# TopLevel.net
KiCad netlist of a schematic drawn in Altium Designer
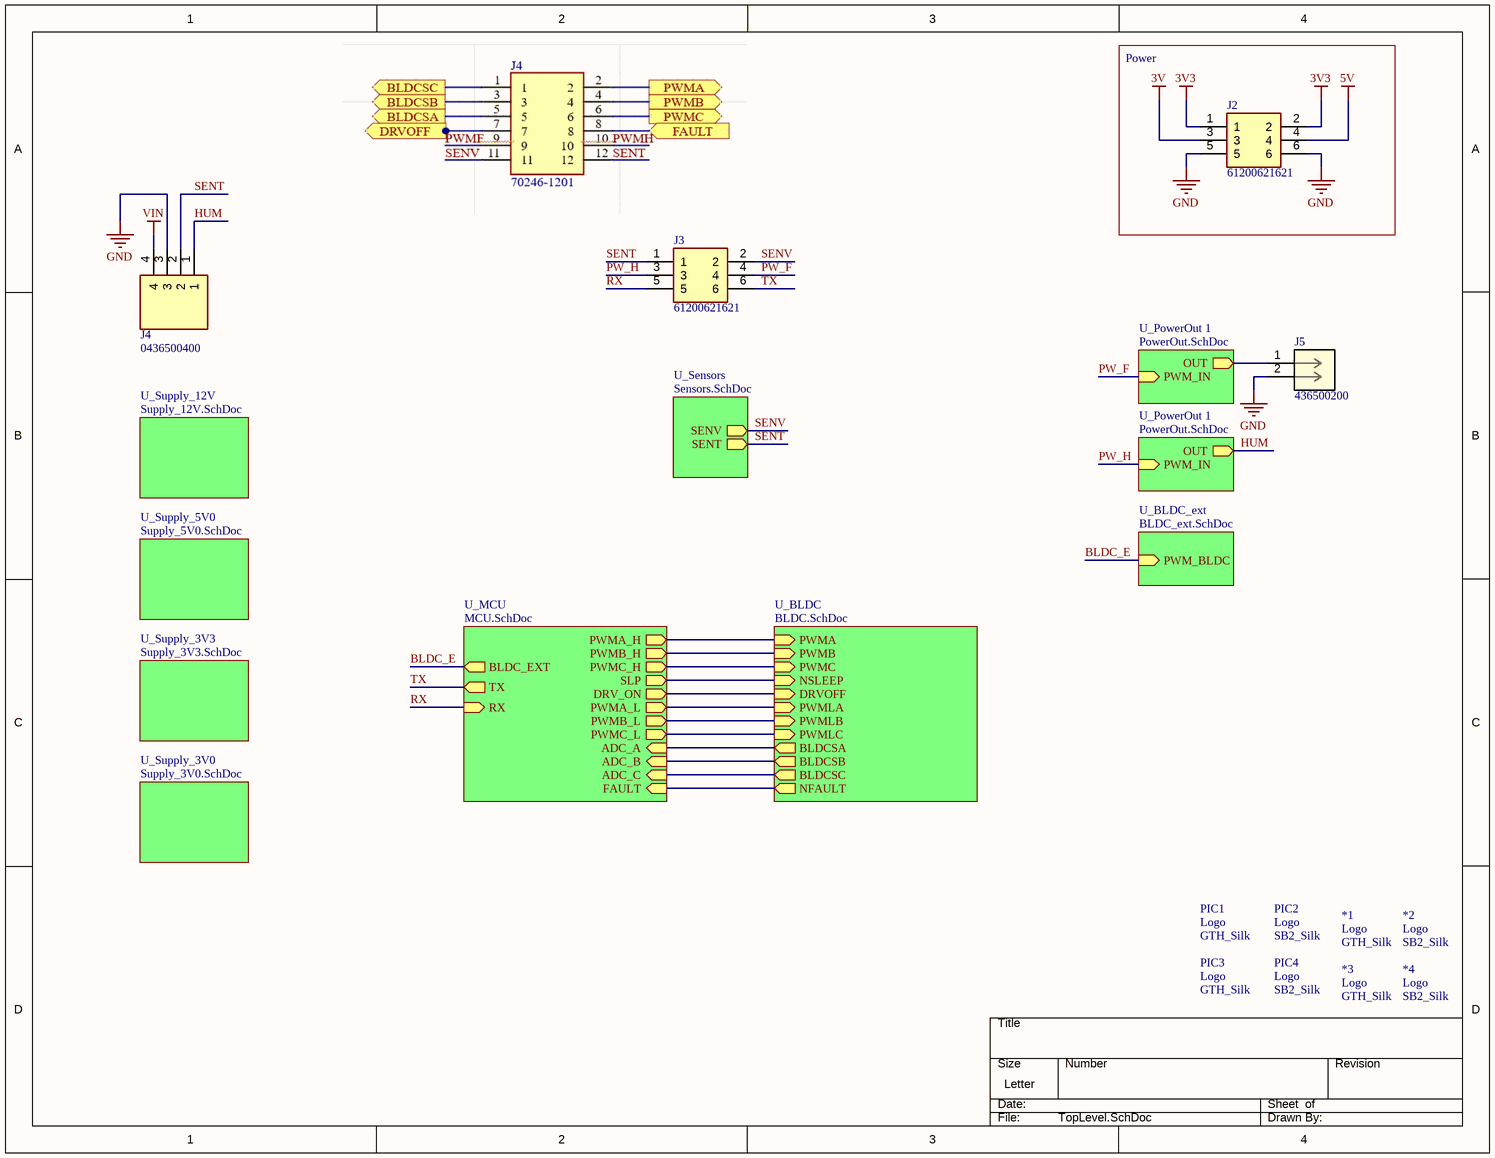
[diagram p0: TopLevel.SchDoc]

(export (version "E")
  (design (tool "Eeschema 10.0.6"))
  (components
    (comp (ref "*1")
      (value "GTH_Silk")
      (footprint "TECHHUB_SILK")
      (libsource (lib "LogoGIBIC") (part "GTH_Silk"))
    )
    (comp (ref "*2")
      (value "SB2_Silk")
      (footprint "SMARTBEDDING2_SILK")
      (libsource (lib "LogoGIBIC") (part "SB2_Silk"))
    )
    (comp (ref "*3")
      (value "GTH_Silk")
      (footprint "TECHHUB_SILK")
      (libsource (lib "LogoGIBIC") (part "GTH_Silk"))
    )
    (comp (ref "*4")
      (value "SB2_Silk")
      (footprint "SMARTBEDDING2_SILK")
      (libsource (lib "LogoGIBIC") (part "SB2_Silk"))
    )
    (comp (ref "J2")
      (value "61200621621")
      (footprint "SHDR6W64P254_2X3_1528X910X910P")
      (description "Wurth Elektronik PCB Header WR-BHD, 6 Way, 2.54mm Pitch, 2 Row, Straight, Through Hole")
      (fields (field (name "MOUSER PART NUMBER") "710-61200621621"))
      (libsource (lib "61200621621") (part "61200621621"))
    )
    (comp (ref "J3")
      (value "61200621621")
      (footprint "SHDR6W64P254_2X3_1528X910X910P")
      (description "Wurth Elektronik PCB Header WR-BHD, 6 Way, 2.54mm Pitch, 2 Row, Straight, Through Hole")
      (fields (field (name "MOUSER PART NUMBER") "710-61200621621"))
      (libsource (lib "61200621621") (part "61200621621"))
    )
    (comp (ref "J4")
      (value "0436500400")
      (footprint "MOLEX_0436500400:MOLEX_0436500400")
      (description "Micro-fit 3.0 Connector, 4 Circuit Single Row, Right Angle Throughhole PCB, Snap-In Peg")
      (fields (field (name "MF") "Molex"))
      (libsource (lib "0436500400") (part "0436500400"))
    )
    (comp (ref "J5")
      (value "436500200")
      (footprint "CONN_SD-43650-001_02_MOL")
      (description "No Description Available")
      (libsource (lib "436500200") (part "436500200"))
    )
    (comp (ref "PIC1")
      (value "GTH_Silk")
      (footprint "TECHHUB_SILK")
      (libsource (lib "LogoGIBIC") (part "GTH_Silk"))
    )
    (comp (ref "PIC2")
      (value "SB2_Silk")
      (footprint "SMARTBEDDING2_SILK")
      (libsource (lib "LogoGIBIC") (part "SB2_Silk"))
    )
    (comp (ref "PIC3")
      (value "GTH_Silk")
      (footprint "TECHHUB_SILK")
      (libsource (lib "LogoGIBIC") (part "GTH_Silk"))
    )
    (comp (ref "PIC4")
      (value "SB2_Silk")
      (footprint "SMARTBEDDING2_SILK")
      (libsource (lib "LogoGIBIC") (part "SB2_Silk"))
    )
  )
  (nets
    (net (code "6") (name "/HUM") (class "Default")
      (node (ref "J4") (pin "1") (pinfunction "1_1") (pintype "passive"))
    )
    (net (code "8") (name "/OUT") (class "Default")
      (node (ref "J5") (pin "1") (pinfunction "1_1") (pintype "passive"))
    )
    (net (code "15") (name "/PW_F") (class "Default")
      (node (ref "J3") (pin "4") (pinfunction "4_4") (pintype "passive"))
    )
    (net (code "16") (name "/PW_H") (class "Default")
      (node (ref "J3") (pin "3") (pinfunction "3_3") (pintype "passive"))
    )
    (net (code "17") (name "/RX") (class "Default")
      (node (ref "J3") (pin "5") (pinfunction "5_5") (pintype "passive"))
    )
    (net (code "18") (name "/SENT") (class "Default")
      (node (ref "J3") (pin "1") (pinfunction "1_1") (pintype "passive"))
      (node (ref "J4") (pin "2") (pinfunction "2_2") (pintype "passive"))
    )
    (net (code "19") (name "/SENV") (class "Default")
      (node (ref "J3") (pin "2") (pinfunction "2_2") (pintype "passive"))
    )
    (net (code "21") (name "/TX") (class "Default")
      (node (ref "J3") (pin "6") (pinfunction "6_6") (pintype "passive"))
    )
    (net (code "22") (name "3V") (class "Default")
      (node (ref "J2") (pin "3") (pinfunction "3_3") (pintype "passive"))
    )
    (net (code "23") (name "3V3") (class "Default")
      (node (ref "J2") (pin "1") (pinfunction "1_1") (pintype "passive"))
      (node (ref "J2") (pin "2") (pinfunction "2_2") (pintype "passive"))
    )
    (net (code "24") (name "5V") (class "Default")
      (node (ref "J2") (pin "4") (pinfunction "4_4") (pintype "passive"))
    )
    (net (code "25") (name "GND") (class "Default")
      (node (ref "J2") (pin "5") (pinfunction "5_5") (pintype "passive"))
      (node (ref "J2") (pin "6") (pinfunction "6_6") (pintype "passive"))
      (node (ref "J4") (pin "3") (pinfunction "3_3") (pintype "passive"))
      (node (ref "J5") (pin "2") (pinfunction "2_2") (pintype "passive"))
    )
    (net (code "26") (name "VIN") (class "Default")
      (node (ref "J4") (pin "4") (pinfunction "4_4") (pintype "passive"))
    )
  )
)
